# HeaterMeterLCD.net
KiCad netlist of a schematic drawn in EAGLE
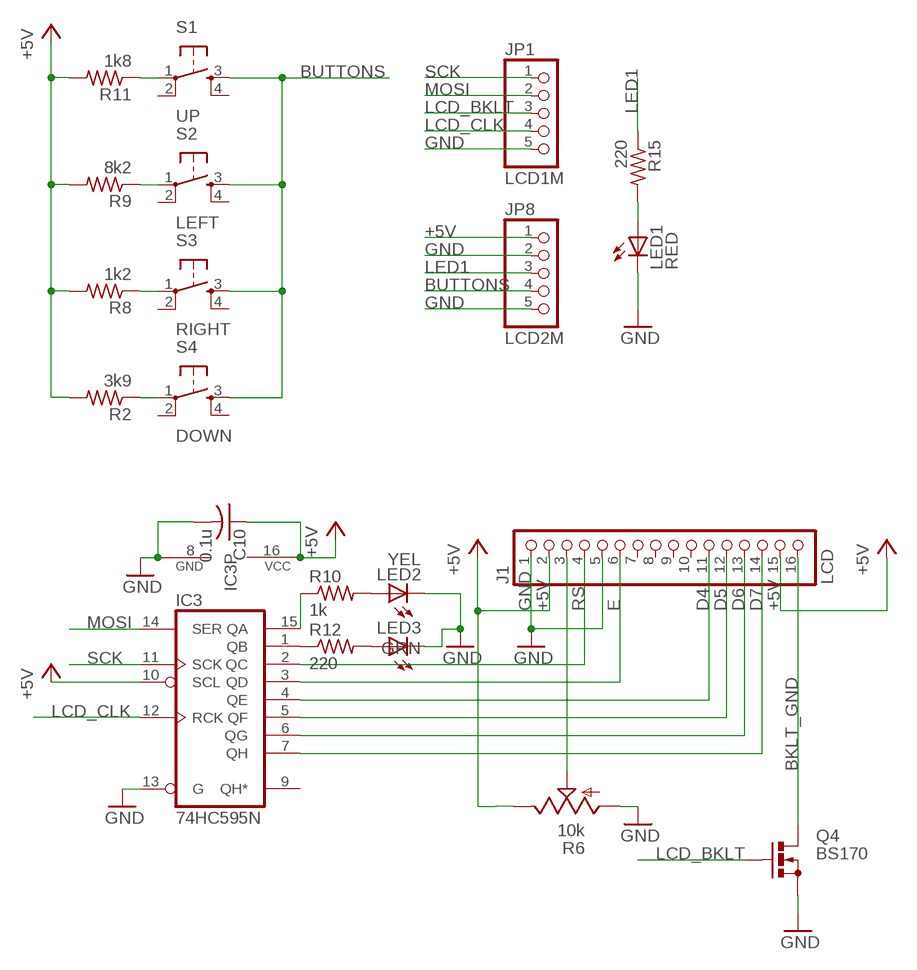
[diagram p0: schematic, sheet 1]

(export (version "E")
  (design (tool "Eeschema 10.0.6"))
  (components
    (comp (ref "C10")
      (value "0.1u")
      (footprint "eagle-import:C025-025X050")
      (libsource (lib "eagle-import") (part "C-US025-025X050"))
    )
    (comp (ref "IC3")
      (value "74HC595N")
      (footprint "eagle-import:DIL16")
      (libsource (lib "eagle-import") (part "74595NLS"))
    )
    (comp (ref "J1")
      (value "LCD")
      (footprint "eagle-import:1X16")
      (libsource (lib "eagle-import") (part "PINHD-1X16"))
    )
    (comp (ref "JP1")
      (value "LCD1M")
      (footprint "eagle-import:1X05")
      (libsource (lib "eagle-import") (part "PINHD-1X5"))
    )
    (comp (ref "JP8")
      (value "LCD2M")
      (footprint "eagle-import:1X05")
      (libsource (lib "eagle-import") (part "PINHD-1X5"))
    )
    (comp (ref "LED1")
      (value "RED")
      (footprint "eagle-import:LED3MM")
      (libsource (lib "eagle-import") (part "LED3MM"))
    )
    (comp (ref "LED2")
      (value "YEL")
      (footprint "eagle-import:LED3MM")
      (libsource (lib "eagle-import") (part "LED3MM"))
    )
    (comp (ref "LED3")
      (value "GRN")
      (footprint "eagle-import:LED3MM")
      (libsource (lib "eagle-import") (part "LED3MM"))
    )
    (comp (ref "Q4")
      (value "BS170")
      (footprint "eagle-import:SOT54E")
      (libsource (lib "eagle-import") (part "BS170"))
    )
    (comp (ref "R2")
      (value "3k9")
      (footprint "eagle-import:0204_7")
      (libsource (lib "eagle-import") (part "R-US_0204/7"))
    )
    (comp (ref "R6")
      (value "10k")
      (footprint "eagle-import:POT-CT6-SIDE")
      (libsource (lib "eagle-import") (part "POTENTIOMETERSIDE"))
    )
    (comp (ref "R8")
      (value "1k2")
      (footprint "eagle-import:0204_7")
      (libsource (lib "eagle-import") (part "R-US_0204/7"))
    )
    (comp (ref "R9")
      (value "8k2")
      (footprint "eagle-import:0204_7")
      (libsource (lib "eagle-import") (part "R-US_0204/7"))
    )
    (comp (ref "R10")
      (value "1k")
      (footprint "eagle-import:0204_7")
      (libsource (lib "eagle-import") (part "R-US_0204/7"))
    )
    (comp (ref "R11")
      (value "1k8")
      (footprint "eagle-import:0204_7")
      (libsource (lib "eagle-import") (part "R-US_0204/7"))
    )
    (comp (ref "R12")
      (value "220")
      (footprint "eagle-import:0204_7")
      (libsource (lib "eagle-import") (part "R-US_0204/7"))
    )
    (comp (ref "R15")
      (value "220")
      (footprint "eagle-import:0204_7")
      (libsource (lib "eagle-import") (part "R-US_0204/7"))
    )
    (comp (ref "S1")
      (value "UP")
      (footprint "eagle-import:TACT-OMRON-12MM")
      (libsource (lib "eagle-import") (part "TACTILE"))
    )
    (comp (ref "S2")
      (value "LEFT")
      (footprint "eagle-import:TACT-OMRON-12MM")
      (libsource (lib "eagle-import") (part "TACTILE"))
    )
    (comp (ref "S3")
      (value "RIGHT")
      (footprint "eagle-import:TACT-OMRON-12MM")
      (libsource (lib "eagle-import") (part "TACTILE"))
    )
    (comp (ref "S4")
      (value "DOWN")
      (footprint "eagle-import:TACT-OMRON-12MM")
      (libsource (lib "eagle-import") (part "TACTILE"))
    )
  )
  (nets
    (net (code "1") (name "+5V") (class "Default")
      (node (ref "C10") (pin "1") (pinfunction "1_1") (pintype "passive"))
      (node (ref "IC3") (pin "10") (pinfunction "SCL_10") (pintype "input"))
      (node (ref "IC3") (pin "16") (pinfunction "VCC_16") (pintype "power_in"))
      (node (ref "J1") (pin "15") (pinfunction "15_15") (pintype "passive"))
      (node (ref "J1") (pin "2") (pinfunction "2_2") (pintype "passive"))
      (node (ref "JP8") (pin "1") (pinfunction "1_1") (pintype "passive"))
      (node (ref "R11") (pin "2") (pinfunction "2_2") (pintype "passive"))
      (node (ref "R2") (pin "2") (pinfunction "2_2") (pintype "passive"))
      (node (ref "R6") (pin "E") (pinfunction "E_E") (pintype "passive"))
      (node (ref "R8") (pin "2") (pinfunction "2_2") (pintype "passive"))
      (node (ref "R9") (pin "2") (pinfunction "2_2") (pintype "passive"))
    )
    (net (code "2") (name "/BKLT_GND") (class "Default")
      (node (ref "J1") (pin "16") (pinfunction "16_16") (pintype "passive"))
      (node (ref "Q4") (pin "D") (pinfunction "D_D") (pintype "passive"))
    )
    (net (code "3") (name "/BUTTONS") (class "Default")
      (node (ref "JP8") (pin "4") (pinfunction "4_4") (pintype "passive"))
      (node (ref "S1") (pin "3") (pinfunction "3_3") (pintype "passive"))
      (node (ref "S2") (pin "3") (pinfunction "3_3") (pintype "passive"))
      (node (ref "S3") (pin "3") (pinfunction "3_3") (pintype "passive"))
      (node (ref "S4") (pin "3") (pinfunction "3_3") (pintype "passive"))
    )
    (net (code "4") (name "/D4") (class "Default")
      (node (ref "IC3") (pin "4") (pinfunction "QE_4") (pintype "tri_state"))
      (node (ref "J1") (pin "11") (pinfunction "11_11") (pintype "passive"))
    )
    (net (code "5") (name "/D5") (class "Default")
      (node (ref "IC3") (pin "5") (pinfunction "QF_5") (pintype "tri_state"))
      (node (ref "J1") (pin "12") (pinfunction "12_12") (pintype "passive"))
    )
    (net (code "6") (name "/D6") (class "Default")
      (node (ref "IC3") (pin "6") (pinfunction "QG_6") (pintype "tri_state"))
      (node (ref "J1") (pin "13") (pinfunction "13_13") (pintype "passive"))
    )
    (net (code "7") (name "/D7") (class "Default")
      (node (ref "IC3") (pin "7") (pinfunction "QH_7") (pintype "tri_state"))
      (node (ref "J1") (pin "14") (pinfunction "14_14") (pintype "passive"))
    )
    (net (code "8") (name "/E") (class "Default")
      (node (ref "IC3") (pin "3") (pinfunction "QD_3") (pintype "tri_state"))
      (node (ref "J1") (pin "6") (pinfunction "6_6") (pintype "passive"))
    )
    (net (code "9") (name "/LCD_BKLT") (class "Default")
      (node (ref "JP1") (pin "3") (pinfunction "3_3") (pintype "passive"))
      (node (ref "Q4") (pin "G") (pinfunction "G_G") (pintype "passive"))
    )
    (net (code "10") (name "/LCD_CLK") (class "Default")
      (node (ref "IC3") (pin "12") (pinfunction "RCK_12") (pintype "input"))
      (node (ref "JP1") (pin "4") (pinfunction "4_4") (pintype "passive"))
    )
    (net (code "11") (name "/LED1") (class "Default")
      (node (ref "JP8") (pin "3") (pinfunction "3_3") (pintype "passive"))
      (node (ref "R15") (pin "1") (pinfunction "1_1") (pintype "passive"))
    )
    (net (code "12") (name "/MOSI") (class "Default")
      (node (ref "IC3") (pin "14") (pinfunction "SER_14") (pintype "input"))
      (node (ref "JP1") (pin "2") (pinfunction "2_2") (pintype "passive"))
    )
    (net (code "13") (name "/RS") (class "Default")
      (node (ref "IC3") (pin "2") (pinfunction "QC_2") (pintype "tri_state"))
      (node (ref "J1") (pin "4") (pinfunction "4_4") (pintype "passive"))
    )
    (net (code "14") (name "/SCK") (class "Default")
      (node (ref "IC3") (pin "11") (pinfunction "SCK_11") (pintype "input"))
      (node (ref "JP1") (pin "1") (pinfunction "1_1") (pintype "passive"))
    )
    (net (code "15") (name "GND") (class "Default")
      (node (ref "C10") (pin "2") (pinfunction "2_2") (pintype "passive"))
      (node (ref "IC3") (pin "13") (pinfunction "G_13") (pintype "input"))
      (node (ref "IC3") (pin "8") (pinfunction "GND_8") (pintype "power_in"))
      (node (ref "J1") (pin "1") (pinfunction "1_1") (pintype "passive"))
      (node (ref "J1") (pin "5") (pinfunction "5_5") (pintype "passive"))
      (node (ref "JP1") (pin "5") (pinfunction "5_5") (pintype "passive"))
      (node (ref "JP8") (pin "2") (pinfunction "2_2") (pintype "passive"))
      (node (ref "JP8") (pin "5") (pinfunction "5_5") (pintype "passive"))
      (node (ref "LED1") (pin "K") (pinfunction "C_K") (pintype "passive"))
      (node (ref "LED2") (pin "K") (pinfunction "C_K") (pintype "passive"))
      (node (ref "LED3") (pin "K") (pinfunction "C_K") (pintype "passive"))
      (node (ref "Q4") (pin "S") (pinfunction "S_S") (pintype "passive"))
      (node (ref "R6") (pin "A") (pinfunction "A_A") (pintype "passive"))
    )
    (net (code "16") (name "Net-(IC3A-QA)") (class "Default")
      (node (ref "IC3") (pin "15") (pinfunction "QA_15") (pintype "tri_state"))
      (node (ref "R10") (pin "1") (pinfunction "1_1") (pintype "passive"))
    )
    (net (code "17") (name "Net-(IC3A-QB)") (class "Default")
      (node (ref "IC3") (pin "1") (pinfunction "QB_1") (pintype "tri_state"))
      (node (ref "R12") (pin "1") (pinfunction "1_1") (pintype "passive"))
    )
    (net (code "18") (name "Net-(J1-Pad3)") (class "Default")
      (node (ref "J1") (pin "3") (pinfunction "3_3") (pintype "passive"))
      (node (ref "R6") (pin "S") (pinfunction "S_S") (pintype "passive"))
    )
    (net (code "19") (name "Net-(LED1-PadA)") (class "Default")
      (node (ref "LED1") (pin "A") (pinfunction "A_A") (pintype "passive"))
      (node (ref "R15") (pin "2") (pinfunction "2_2") (pintype "passive"))
    )
    (net (code "20") (name "Net-(LED2-PadA)") (class "Default")
      (node (ref "LED2") (pin "A") (pinfunction "A_A") (pintype "passive"))
      (node (ref "R10") (pin "2") (pinfunction "2_2") (pintype "passive"))
    )
    (net (code "21") (name "Net-(LED3-PadA)") (class "Default")
      (node (ref "LED3") (pin "A") (pinfunction "A_A") (pintype "passive"))
      (node (ref "R12") (pin "2") (pinfunction "2_2") (pintype "passive"))
    )
    (net (code "22") (name "Net-(R2-Pad1)") (class "Default")
      (node (ref "R2") (pin "1") (pinfunction "1_1") (pintype "passive"))
      (node (ref "S4") (pin "1") (pinfunction "1_1") (pintype "passive"))
    )
    (net (code "23") (name "Net-(R8-Pad1)") (class "Default")
      (node (ref "R8") (pin "1") (pinfunction "1_1") (pintype "passive"))
      (node (ref "S3") (pin "1") (pinfunction "1_1") (pintype "passive"))
    )
    (net (code "24") (name "Net-(R9-Pad1)") (class "Default")
      (node (ref "R9") (pin "1") (pinfunction "1_1") (pintype "passive"))
      (node (ref "S2") (pin "1") (pinfunction "1_1") (pintype "passive"))
    )
    (net (code "25") (name "Net-(R11-Pad1)") (class "Default")
      (node (ref "R11") (pin "1") (pinfunction "1_1") (pintype "passive"))
      (node (ref "S1") (pin "1") (pinfunction "1_1") (pintype "passive"))
    )
    (net (code "26") (name "unconnected-(IC3A-QH*-Pad9)") (class "Default")
      (node (ref "IC3") (pin "9") (pinfunction "QH*_9") (pintype "tri_state"))
    )
    (net (code "27") (name "unconnected-(J1-Pad7)") (class "Default")
      (node (ref "J1") (pin "7") (pinfunction "7_7") (pintype "passive"))
    )
    (net (code "28") (name "unconnected-(J1-Pad8)") (class "Default")
      (node (ref "J1") (pin "8") (pinfunction "8_8") (pintype "passive"))
    )
    (net (code "29") (name "unconnected-(J1-Pad9)") (class "Default")
      (node (ref "J1") (pin "9") (pinfunction "9_9") (pintype "passive"))
    )
    (net (code "30") (name "unconnected-(J1-Pad10)") (class "Default")
      (node (ref "J1") (pin "10") (pinfunction "10_10") (pintype "passive"))
    )
    (net (code "31") (name "unconnected-(S1-Pad2)") (class "Default")
      (node (ref "S1") (pin "2") (pinfunction "2_2") (pintype "passive"))
    )
    (net (code "32") (name "unconnected-(S1-Pad4)") (class "Default")
      (node (ref "S1") (pin "4") (pinfunction "4_4") (pintype "passive"))
    )
    (net (code "33") (name "unconnected-(S2-Pad2)") (class "Default")
      (node (ref "S2") (pin "2") (pinfunction "2_2") (pintype "passive"))
    )
    (net (code "34") (name "unconnected-(S2-Pad4)") (class "Default")
      (node (ref "S2") (pin "4") (pinfunction "4_4") (pintype "passive"))
    )
    (net (code "35") (name "unconnected-(S3-Pad2)") (class "Default")
      (node (ref "S3") (pin "2") (pinfunction "2_2") (pintype "passive"))
    )
    (net (code "36") (name "unconnected-(S3-Pad4)") (class "Default")
      (node (ref "S3") (pin "4") (pinfunction "4_4") (pintype "passive"))
    )
    (net (code "37") (name "unconnected-(S4-Pad2)") (class "Default")
      (node (ref "S4") (pin "2") (pinfunction "2_2") (pintype "passive"))
    )
    (net (code "38") (name "unconnected-(S4-Pad4)") (class "Default")
      (node (ref "S4") (pin "4") (pinfunction "4_4") (pintype "passive"))
    )
  )
)
